# CH55xFanCtl.net
KiCad netlist of a schematic drawn in EasyEDA Pro
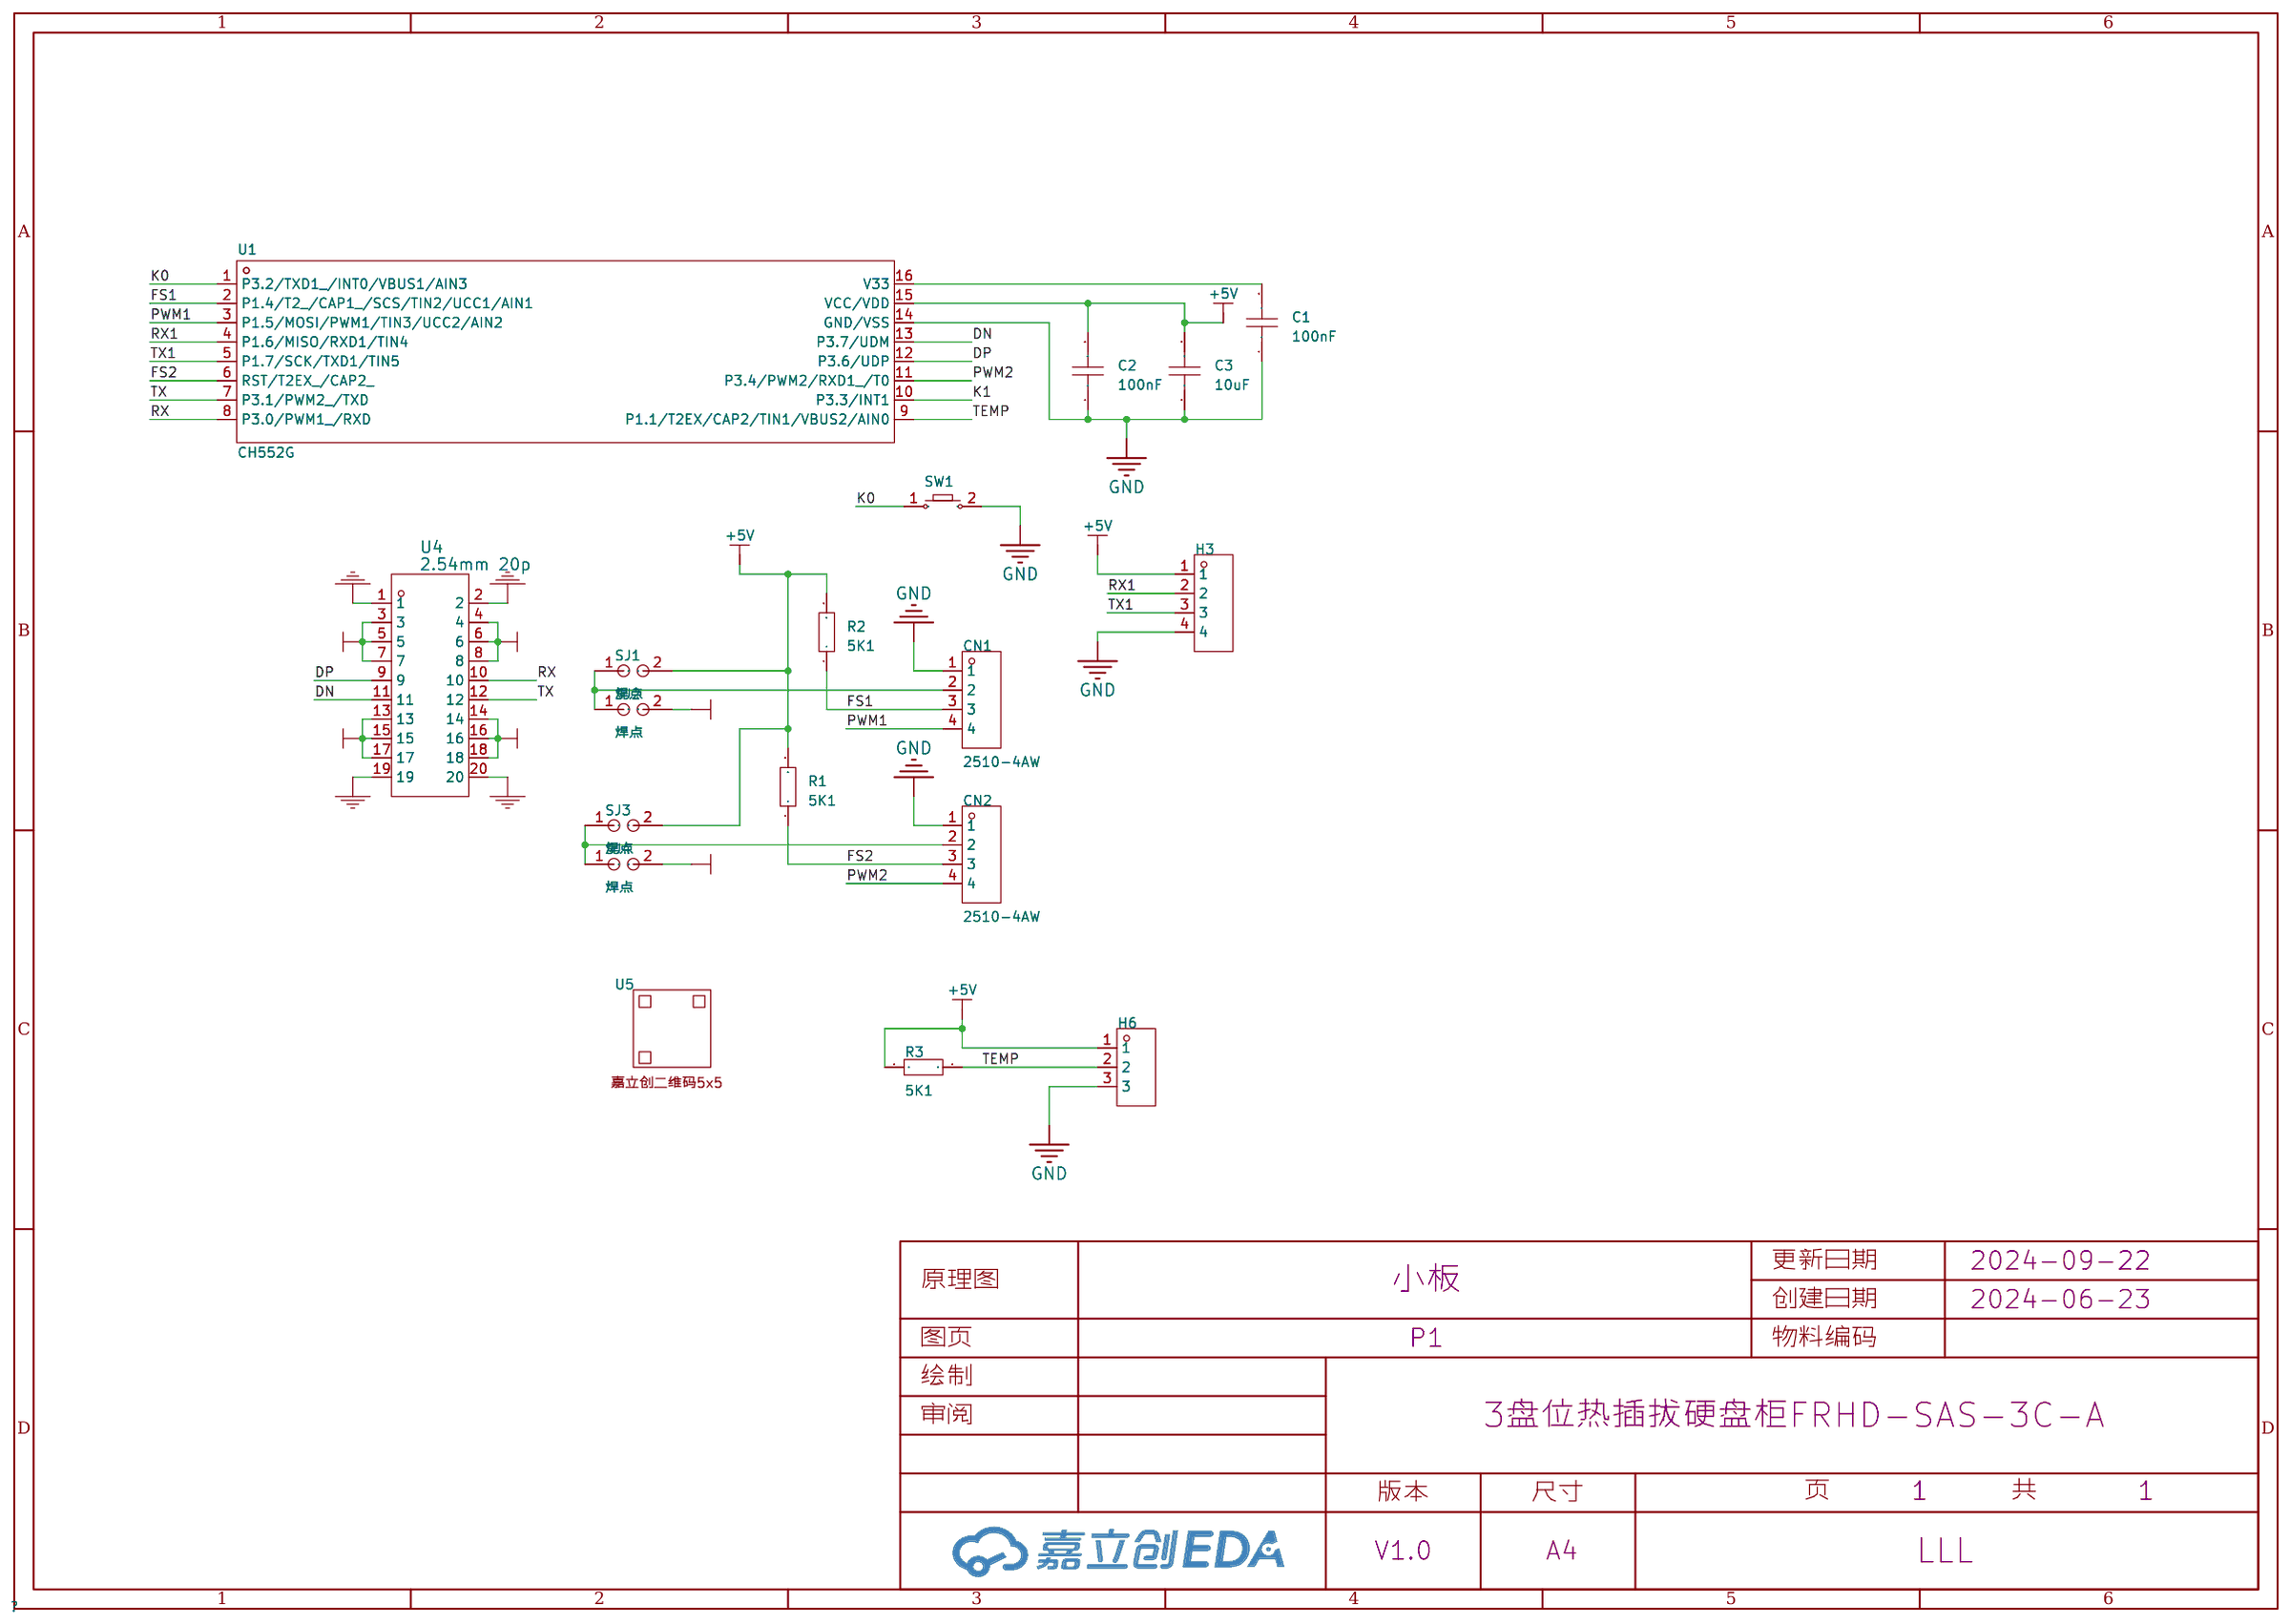
[diagram p0: schematic sheet]

(export (version "E")
  (design (tool "Eeschema 10.0.6"))
  (components
    (comp (ref "C1")
      (value "100nF")
      (footprint "easyedapro:C0805")
      (libsource (lib "easyedapro") (part "CapAcitance"))
    )
    (comp (ref "C2")
      (value "100nF")
      (footprint "easyedapro:C0805")
      (libsource (lib "easyedapro") (part "CapAcitance"))
    )
    (comp (ref "C3")
      (value "10uF")
      (footprint "easyedapro:C0805")
      (libsource (lib "easyedapro") (part "CapAcitance"))
    )
    (comp (ref "CN1")
      (value "2510-4AW")
      (footprint "easyedapro:CONN-TH_2510-4AW")
      (description "插针结构:1x4P;间距:2.54mm;安装方式:弯插;参考系列:-;总PIN数:4P;排数:1;每排PIN数:4;行距:-;额定电流:3A;工作温度范围:-25°C~+85°C;")
      (fields (field (name "Manufacturer") "CAX(创都)"))
      (libsource (lib "easyedapro") (part "2510-4AW"))
    )
    (comp (ref "CN2")
      (value "2510-4AW")
      (footprint "easyedapro:CONN-TH_2510-4AW")
      (description "插针结构:1x4P;间距:2.54mm;安装方式:弯插;参考系列:-;总PIN数:4P;排数:1;每排PIN数:4;行距:-;额定电流:3A;工作温度范围:-25°C~+85°C;")
      (fields (field (name "Manufacturer") "CAX(创都)"))
      (libsource (lib "easyedapro") (part "2510-4AW"))
    )
    (comp (ref "H3")
      (value "~")
      (footprint "easyedapro:HDR-TH_4P-P2.54-V-F")
      (libsource (lib "easyedapro") (part "2.54-1*4P母"))
    )
    (comp (ref "H6")
      (value "~")
      (footprint "easyedapro:HDR-TH_3P-P2.54-V-F")
      (libsource (lib "easyedapro") (part "PM254V-11-03-H85"))
    )
    (comp (ref "R1") (value "5K1") (footprint "easyedapro:R0805") (libsource (lib "easyedapro") (part "电阻")))
    (comp (ref "R2") (value "5K1") (footprint "easyedapro:R0805") (libsource (lib "easyedapro") (part "电阻")))
    (comp (ref "R3") (value "5K1") (footprint "easyedapro:R0805") (libsource (lib "easyedapro") (part "电阻")))
    (comp (ref "SJ1")
      (value "焊点")
      (footprint "easyedapro:TOGO_MODE")
      (libsource (lib "easyedapro") (part "焊点"))
    )
    (comp (ref "SJ2")
      (value "焊点")
      (footprint "easyedapro:TOGO_MODE")
      (libsource (lib "easyedapro") (part "焊点"))
    )
    (comp (ref "SJ3")
      (value "焊点")
      (footprint "easyedapro:TOGO_MODE")
      (libsource (lib "easyedapro") (part "焊点"))
    )
    (comp (ref "SJ4")
      (value "焊点")
      (footprint "easyedapro:TOGO_MODE")
      (libsource (lib "easyedapro") (part "焊点"))
    )
    (comp (ref "SW1")
      (value "~")
      (footprint "easyedapro:Key_SMD_3.6x6.1x2.5")
      (libsource (lib "easyedapro") (part "轻触按键x2"))
    )
    (comp (ref "U1")
      (value "CH552G")
      (footprint "easyedapro:SOP-16_L10.0-W3.9-P1.27-LS6.0-BL")
      (description "CPU内核:51系列;程序存储容量:16KB;RAM总容量:1.25KB;GPIO端口数量:-;工作电压范围:3.3V~5V;CPU最大主频:24MHz;程序存储器类型:FLASH;")
      (fields (field (name "Manufacturer") "WCH(南京沁恒)"))
      (libsource (lib "easyedapro") (part "CH552G"))
    )
    (comp (ref "U4")
      (value "2.54mm 20p")
      (footprint "easyedapro:2.54MM 20P")
      (libsource (lib "easyedapro") (part "2.54mm 20p"))
    )
    (comp (ref "U5")
      (value "~")
      (footprint "easyedapro:JLC-QRCODE-5x5")
      (libsource (lib "easyedapro") (part "嘉立创二维码5x5"))
    )
  )
  (nets
    (net (code "1") (name "+5V") (class "Default")
      (node (ref "C2") (pin "2") (pinfunction "2_2") (pintype "input"))
      (node (ref "C3") (pin "2") (pinfunction "2_2") (pintype "input"))
      (node (ref "H3") (pin "1") (pinfunction "1_1") (pintype "unspecified"))
      (node (ref "H6") (pin "1") (pinfunction "1_1") (pintype "unspecified"))
      (node (ref "R1") (pin "2") (pinfunction "2_2") (pintype "input"))
      (node (ref "R2") (pin "2") (pinfunction "2_2") (pintype "input"))
      (node (ref "R3") (pin "2") (pinfunction "2_2") (pintype "input"))
      (node (ref "SJ1") (pin "2") (pinfunction "2_2") (pintype "input"))
      (node (ref "SJ3") (pin "2") (pinfunction "2_2") (pintype "input"))
      (node (ref "U1") (pin "15") (pinfunction "VCC/VDD_15") (pintype "unspecified"))
      (node (ref "U4") (pin "13") (pinfunction "13_13") (pintype "input"))
      (node (ref "U4") (pin "14") (pinfunction "14_14") (pintype "input"))
      (node (ref "U4") (pin "15") (pinfunction "15_15") (pintype "input"))
      (node (ref "U4") (pin "16") (pinfunction "16_16") (pintype "input"))
      (node (ref "U4") (pin "17") (pinfunction "17_17") (pintype "input"))
      (node (ref "U4") (pin "18") (pinfunction "18_18") (pintype "input"))
    )
    (net (code "2") (name "+12V") (class "Default")
      (node (ref "SJ2") (pin "2") (pinfunction "2_2") (pintype "input"))
      (node (ref "SJ4") (pin "2") (pinfunction "2_2") (pintype "input"))
      (node (ref "U4") (pin "3") (pinfunction "3_3") (pintype "input"))
      (node (ref "U4") (pin "4") (pinfunction "4_4") (pintype "input"))
      (node (ref "U4") (pin "5") (pinfunction "5_5") (pintype "input"))
      (node (ref "U4") (pin "6") (pinfunction "6_6") (pintype "input"))
      (node (ref "U4") (pin "7") (pinfunction "7_7") (pintype "input"))
      (node (ref "U4") (pin "8") (pinfunction "8_8") (pintype "input"))
    )
    (net (code "3") (name "/DN") (class "Default")
      (node (ref "U1") (pin "13") (pinfunction "P3.7/UDM_13") (pintype "unspecified"))
      (node (ref "U4") (pin "11") (pinfunction "11_11") (pintype "input"))
    )
    (net (code "4") (name "/DP") (class "Default")
      (node (ref "U1") (pin "12") (pinfunction "P3.6/UDP_12") (pintype "unspecified"))
      (node (ref "U4") (pin "9") (pinfunction "9_9") (pintype "input"))
    )
    (net (code "5") (name "/FS1") (class "Default")
      (node (ref "CN1") (pin "3") (pinfunction "3_3") (pintype "unspecified"))
      (node (ref "R2") (pin "1") (pinfunction "1_1") (pintype "input"))
      (node (ref "U1") (pin "2") (pinfunction "P1.4/T2_/CAP1_/SCS/TIN2/UCC1/AIN1_2") (pintype "unspecified"))
    )
    (net (code "6") (name "/FS2") (class "Default")
      (node (ref "CN2") (pin "3") (pinfunction "3_3") (pintype "unspecified"))
      (node (ref "R1") (pin "1") (pinfunction "1_1") (pintype "input"))
      (node (ref "U1") (pin "6") (pinfunction "RST/T2EX_/CAP2__6") (pintype "unspecified"))
    )
    (net (code "7") (name "/K0") (class "Default")
      (node (ref "SW1") (pin "1") (pinfunction "1_1") (pintype "input"))
      (node (ref "U1") (pin "1") (pinfunction "P3.2/TXD1_/INT0/VBUS1/AIN3_1") (pintype "unspecified"))
    )
    (net (code "8") (name "/K1") (class "Default")
      (node (ref "U1") (pin "10") (pinfunction "P3.3/INT1_10") (pintype "unspecified"))
    )
    (net (code "9") (name "/PWM1") (class "Default")
      (node (ref "CN1") (pin "4") (pinfunction "4_4") (pintype "unspecified"))
      (node (ref "U1") (pin "3") (pinfunction "P1.5/MOSI/PWM1/TIN3/UCC2/AIN2_3") (pintype "unspecified"))
    )
    (net (code "10") (name "/PWM2") (class "Default")
      (node (ref "CN2") (pin "4") (pinfunction "4_4") (pintype "unspecified"))
      (node (ref "U1") (pin "11") (pinfunction "P3.4/PWM2/RXD1_/T0_11") (pintype "unspecified"))
    )
    (net (code "11") (name "/RX") (class "Default")
      (node (ref "U1") (pin "8") (pinfunction "P3.0/PWM1_/RXD_8") (pintype "unspecified"))
      (node (ref "U4") (pin "10") (pinfunction "10_10") (pintype "input"))
    )
    (net (code "12") (name "/RX1") (class "Default")
      (node (ref "H3") (pin "2") (pinfunction "2_2") (pintype "unspecified"))
      (node (ref "U1") (pin "4") (pinfunction "P1.6/MISO/RXD1/TIN4_4") (pintype "unspecified"))
    )
    (net (code "13") (name "/TEMP") (class "Default")
      (node (ref "H6") (pin "2") (pinfunction "2_2") (pintype "unspecified"))
      (node (ref "R3") (pin "1") (pinfunction "1_1") (pintype "input"))
      (node (ref "U1") (pin "9") (pinfunction "P1.1/T2EX/CAP2/TIN1/VBUS2/AIN0_9") (pintype "unspecified"))
    )
    (net (code "14") (name "/TX") (class "Default")
      (node (ref "U1") (pin "7") (pinfunction "P3.1/PWM2_/TXD_7") (pintype "unspecified"))
      (node (ref "U4") (pin "12") (pinfunction "12_12") (pintype "input"))
    )
    (net (code "15") (name "/TX1") (class "Default")
      (node (ref "H3") (pin "3") (pinfunction "3_3") (pintype "unspecified"))
      (node (ref "U1") (pin "5") (pinfunction "P1.7/SCK/TXD1/TIN5_5") (pintype "unspecified"))
    )
    (net (code "16") (name "GND") (class "Default")
      (node (ref "C1") (pin "1") (pinfunction "1_1") (pintype "input"))
      (node (ref "C2") (pin "1") (pinfunction "1_1") (pintype "input"))
      (node (ref "C3") (pin "1") (pinfunction "1_1") (pintype "input"))
      (node (ref "CN1") (pin "1") (pinfunction "1_1") (pintype "unspecified"))
      (node (ref "CN2") (pin "1") (pinfunction "1_1") (pintype "unspecified"))
      (node (ref "H3") (pin "4") (pinfunction "4_4") (pintype "unspecified"))
      (node (ref "H6") (pin "3") (pinfunction "3_3") (pintype "unspecified"))
      (node (ref "SW1") (pin "2") (pinfunction "2_2") (pintype "input"))
      (node (ref "U1") (pin "14") (pinfunction "GND/VSS_14") (pintype "unspecified"))
      (node (ref "U4") (pin "1") (pinfunction "1_1") (pintype "input"))
      (node (ref "U4") (pin "19") (pinfunction "19_19") (pintype "input"))
      (node (ref "U4") (pin "2") (pinfunction "2_2") (pintype "input"))
      (node (ref "U4") (pin "20") (pinfunction "20_20") (pintype "input"))
    )
    (net (code "17") (name "Net-(CN1-Pad2)") (class "Default")
      (node (ref "CN1") (pin "2") (pinfunction "2_2") (pintype "unspecified"))
      (node (ref "SJ1") (pin "1") (pinfunction "1_1") (pintype "input"))
      (node (ref "SJ2") (pin "1") (pinfunction "1_1") (pintype "input"))
    )
    (net (code "18") (name "Net-(CN2-Pad2)") (class "Default")
      (node (ref "CN2") (pin "2") (pinfunction "2_2") (pintype "unspecified"))
      (node (ref "SJ3") (pin "1") (pinfunction "1_1") (pintype "input"))
      (node (ref "SJ4") (pin "1") (pinfunction "1_1") (pintype "input"))
    )
    (net (code "19") (name "Net-(U1-V33)") (class "Default")
      (node (ref "C1") (pin "2") (pinfunction "2_2") (pintype "input"))
      (node (ref "U1") (pin "16") (pinfunction "V33_16") (pintype "unspecified"))
    )
  )
)
